# flat_bridge.net
KiCad netlist of a schematic drawn in EAGLE
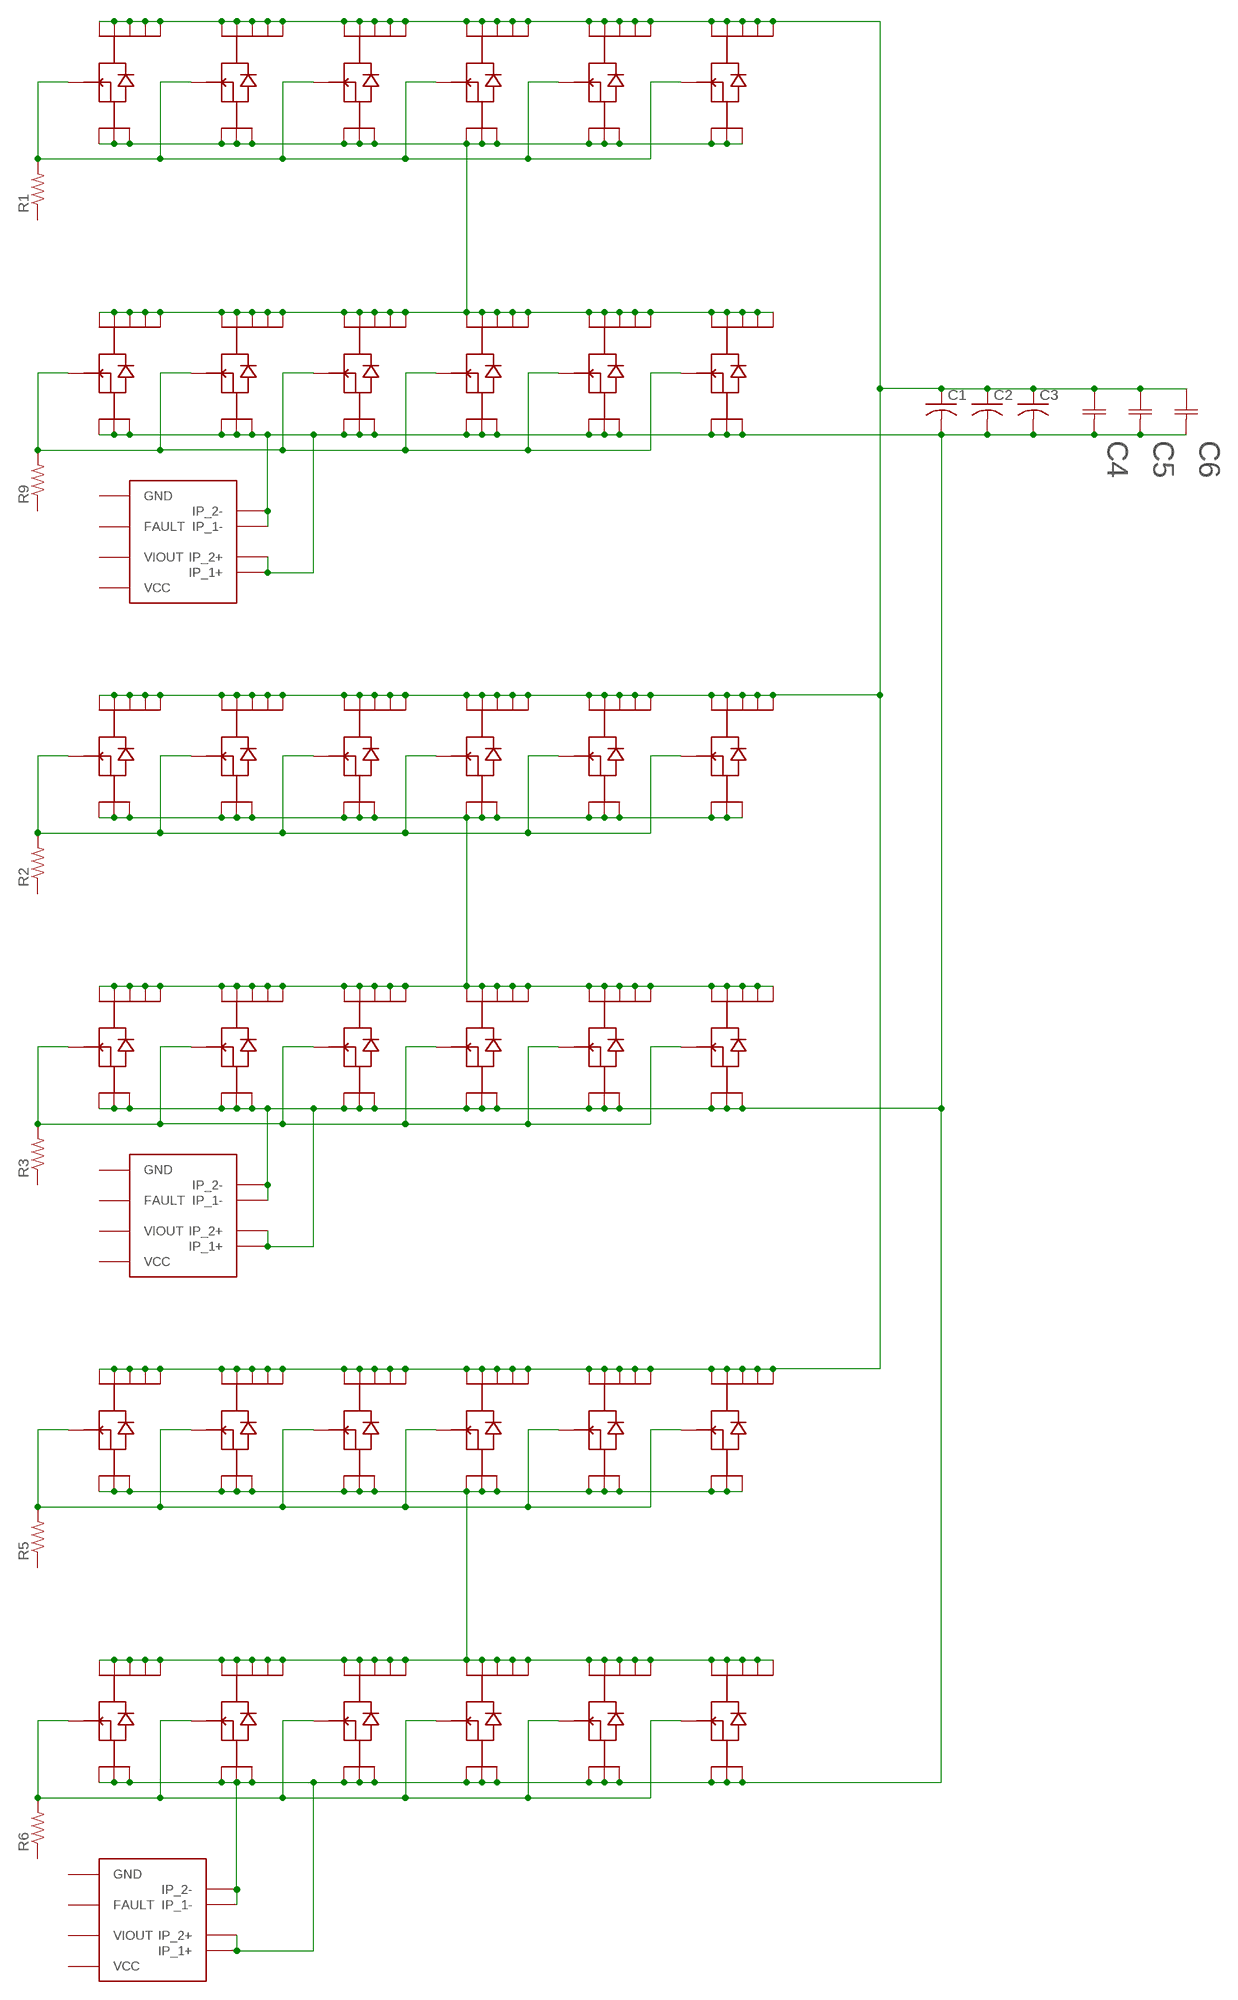
[diagram p0: schematic, sheet 1]

(export (version "E")
  (design (tool "Eeschema 10.0.6"))
  (components
    (comp (ref "C1")
      (value "C-USC2220K")
      (footprint "eagle-import:C2220K")
      (libsource (lib "eagle-import") (part "C-USC2220K"))
    )
    (comp (ref "C2")
      (value "C-USC2220K")
      (footprint "eagle-import:C2220K")
      (libsource (lib "eagle-import") (part "C-USC2220K"))
    )
    (comp (ref "C3")
      (value "C-USC2220K")
      (footprint "eagle-import:C2220K")
      (libsource (lib "eagle-import") (part "C-USC2220K"))
    )
    (comp (ref "C4")
      (value "EEVFK1J471M")
      (footprint "eagle-import:CAP_EEFK_J16")
      (fields (field (name "COPYRIGHT") "Copyright (C) 2015 Accelerated Designs. All rights reserved"))
      (libsource (lib "eagle-import") (part "EEVFK1J471M"))
    )
    (comp (ref "C5")
      (value "EEVFK1J471M")
      (footprint "eagle-import:CAP_EEFK_J16")
      (fields (field (name "COPYRIGHT") "Copyright (C) 2015 Accelerated Designs. All rights reserved"))
      (libsource (lib "eagle-import") (part "EEVFK1J471M"))
    )
    (comp (ref "C6")
      (value "EEVFK1J471M")
      (footprint "eagle-import:CAP_EEFK_J16")
      (fields (field (name "COPYRIGHT") "Copyright (C) 2015 Accelerated Designs. All rights reserved"))
      (libsource (lib "eagle-import") (part "EEVFK1J471M"))
    )
    (comp (ref "R1")
      (value "R-US_R1206")
      (footprint "eagle-import:R1206")
      (libsource (lib "eagle-import") (part "R-US_R1206"))
    )
    (comp (ref "R2")
      (value "R-US_R1206")
      (footprint "eagle-import:R1206")
      (libsource (lib "eagle-import") (part "R-US_R1206"))
    )
    (comp (ref "R3")
      (value "R-US_R1206")
      (footprint "eagle-import:R1206")
      (libsource (lib "eagle-import") (part "R-US_R1206"))
    )
    (comp (ref "R5")
      (value "R-US_R1206")
      (footprint "eagle-import:R1206")
      (libsource (lib "eagle-import") (part "R-US_R1206"))
    )
    (comp (ref "R6")
      (value "R-US_R1206")
      (footprint "eagle-import:R1206")
      (libsource (lib "eagle-import") (part "R-US_R1206"))
    )
    (comp (ref "R9")
      (value "R-US_R1206")
      (footprint "eagle-import:R1206")
      (libsource (lib "eagle-import") (part "R-US_R1206"))
    )
    (comp (ref "U$1")
      (value "TPH2R608NH")
      (footprint "eagle-import:SOP-ADVANCE")
      (libsource (lib "eagle-import") (part "TPH2R608NH"))
    )
    (comp (ref "U$2")
      (value "TPH2R608NH")
      (footprint "eagle-import:SOP-ADVANCE")
      (libsource (lib "eagle-import") (part "TPH2R608NH"))
    )
    (comp (ref "U$3")
      (value "TPH2R608NH")
      (footprint "eagle-import:SOP-ADVANCE")
      (libsource (lib "eagle-import") (part "TPH2R608NH"))
    )
    (comp (ref "U$4")
      (value "TPH2R608NH")
      (footprint "eagle-import:SOP-ADVANCE")
      (libsource (lib "eagle-import") (part "TPH2R608NH"))
    )
    (comp (ref "U$5")
      (value "TPH2R608NH")
      (footprint "eagle-import:SOP-ADVANCE")
      (libsource (lib "eagle-import") (part "TPH2R608NH"))
    )
    (comp (ref "U$6")
      (value "TPH2R608NH")
      (footprint "eagle-import:SOP-ADVANCE")
      (libsource (lib "eagle-import") (part "TPH2R608NH"))
    )
    (comp (ref "U$7")
      (value "ACS711")
      (footprint "eagle-import:SO8")
      (libsource (lib "eagle-import") (part "ACS711"))
    )
    (comp (ref "U$8")
      (value "TPH2R608NH")
      (footprint "eagle-import:SOP-ADVANCE")
      (libsource (lib "eagle-import") (part "TPH2R608NH"))
    )
    (comp (ref "U$9")
      (value "TPH2R608NH")
      (footprint "eagle-import:SOP-ADVANCE")
      (libsource (lib "eagle-import") (part "TPH2R608NH"))
    )
    (comp (ref "U$10")
      (value "TPH2R608NH")
      (footprint "eagle-import:SOP-ADVANCE")
      (libsource (lib "eagle-import") (part "TPH2R608NH"))
    )
    (comp (ref "U$11")
      (value "TPH2R608NH")
      (footprint "eagle-import:SOP-ADVANCE")
      (libsource (lib "eagle-import") (part "TPH2R608NH"))
    )
    (comp (ref "U$12")
      (value "TPH2R608NH")
      (footprint "eagle-import:SOP-ADVANCE")
      (libsource (lib "eagle-import") (part "TPH2R608NH"))
    )
    (comp (ref "U$13")
      (value "TPH2R608NH")
      (footprint "eagle-import:SOP-ADVANCE")
      (libsource (lib "eagle-import") (part "TPH2R608NH"))
    )
    (comp (ref "U$14")
      (value "TPH2R608NH")
      (footprint "eagle-import:SOP-ADVANCE")
      (libsource (lib "eagle-import") (part "TPH2R608NH"))
    )
    (comp (ref "U$15")
      (value "TPH2R608NH")
      (footprint "eagle-import:SOP-ADVANCE")
      (libsource (lib "eagle-import") (part "TPH2R608NH"))
    )
    (comp (ref "U$16")
      (value "TPH2R608NH")
      (footprint "eagle-import:SOP-ADVANCE")
      (libsource (lib "eagle-import") (part "TPH2R608NH"))
    )
    (comp (ref "U$17")
      (value "TPH2R608NH")
      (footprint "eagle-import:SOP-ADVANCE")
      (libsource (lib "eagle-import") (part "TPH2R608NH"))
    )
    (comp (ref "U$18")
      (value "TPH2R608NH")
      (footprint "eagle-import:SOP-ADVANCE")
      (libsource (lib "eagle-import") (part "TPH2R608NH"))
    )
    (comp (ref "U$19")
      (value "TPH2R608NH")
      (footprint "eagle-import:SOP-ADVANCE")
      (libsource (lib "eagle-import") (part "TPH2R608NH"))
    )
    (comp (ref "U$21")
      (value "TPH2R608NH")
      (footprint "eagle-import:SOP-ADVANCE")
      (libsource (lib "eagle-import") (part "TPH2R608NH"))
    )
    (comp (ref "U$22")
      (value "TPH2R608NH")
      (footprint "eagle-import:SOP-ADVANCE")
      (libsource (lib "eagle-import") (part "TPH2R608NH"))
    )
    (comp (ref "U$23")
      (value "TPH2R608NH")
      (footprint "eagle-import:SOP-ADVANCE")
      (libsource (lib "eagle-import") (part "TPH2R608NH"))
    )
    (comp (ref "U$24")
      (value "TPH2R608NH")
      (footprint "eagle-import:SOP-ADVANCE")
      (libsource (lib "eagle-import") (part "TPH2R608NH"))
    )
    (comp (ref "U$25")
      (value "TPH2R608NH")
      (footprint "eagle-import:SOP-ADVANCE")
      (libsource (lib "eagle-import") (part "TPH2R608NH"))
    )
    (comp (ref "U$26")
      (value "TPH2R608NH")
      (footprint "eagle-import:SOP-ADVANCE")
      (libsource (lib "eagle-import") (part "TPH2R608NH"))
    )
    (comp (ref "U$28")
      (value "ACS711")
      (footprint "eagle-import:SO8")
      (libsource (lib "eagle-import") (part "ACS711"))
    )
    (comp (ref "U$29")
      (value "TPH2R608NH")
      (footprint "eagle-import:SOP-ADVANCE")
      (libsource (lib "eagle-import") (part "TPH2R608NH"))
    )
    (comp (ref "U$30")
      (value "TPH2R608NH")
      (footprint "eagle-import:SOP-ADVANCE")
      (libsource (lib "eagle-import") (part "TPH2R608NH"))
    )
    (comp (ref "U$31")
      (value "TPH2R608NH")
      (footprint "eagle-import:SOP-ADVANCE")
      (libsource (lib "eagle-import") (part "TPH2R608NH"))
    )
    (comp (ref "U$32")
      (value "TPH2R608NH")
      (footprint "eagle-import:SOP-ADVANCE")
      (libsource (lib "eagle-import") (part "TPH2R608NH"))
    )
    (comp (ref "U$33")
      (value "TPH2R608NH")
      (footprint "eagle-import:SOP-ADVANCE")
      (libsource (lib "eagle-import") (part "TPH2R608NH"))
    )
    (comp (ref "U$34")
      (value "TPH2R608NH")
      (footprint "eagle-import:SOP-ADVANCE")
      (libsource (lib "eagle-import") (part "TPH2R608NH"))
    )
    (comp (ref "U$35")
      (value "TPH2R608NH")
      (footprint "eagle-import:SOP-ADVANCE")
      (libsource (lib "eagle-import") (part "TPH2R608NH"))
    )
    (comp (ref "U$36")
      (value "TPH2R608NH")
      (footprint "eagle-import:SOP-ADVANCE")
      (libsource (lib "eagle-import") (part "TPH2R608NH"))
    )
    (comp (ref "U$37")
      (value "TPH2R608NH")
      (footprint "eagle-import:SOP-ADVANCE")
      (libsource (lib "eagle-import") (part "TPH2R608NH"))
    )
    (comp (ref "U$38")
      (value "TPH2R608NH")
      (footprint "eagle-import:SOP-ADVANCE")
      (libsource (lib "eagle-import") (part "TPH2R608NH"))
    )
    (comp (ref "U$39")
      (value "TPH2R608NH")
      (footprint "eagle-import:SOP-ADVANCE")
      (libsource (lib "eagle-import") (part "TPH2R608NH"))
    )
    (comp (ref "U$40")
      (value "TPH2R608NH")
      (footprint "eagle-import:SOP-ADVANCE")
      (libsource (lib "eagle-import") (part "TPH2R608NH"))
    )
    (comp (ref "U$42")
      (value "ACS711")
      (footprint "eagle-import:SO8")
      (libsource (lib "eagle-import") (part "ACS711"))
    )
  )
  (nets
    (net (code "1") (name "Net-(C4-11)") (class "Default")
      (node (ref "C1") (pin "1") (pinfunction "1_1") (pintype "passive"))
      (node (ref "C2") (pin "1") (pinfunction "1_1") (pintype "passive"))
      (node (ref "C3") (pin "1") (pinfunction "1_1") (pintype "passive"))
      (node (ref "C4") (pin "1") (pinfunction "11_1") (pintype "passive"))
      (node (ref "C5") (pin "1") (pinfunction "11_1") (pintype "passive"))
      (node (ref "C6") (pin "1") (pinfunction "11_1") (pintype "passive"))
      (node (ref "U$1") (pin "5") (pinfunction "D1_5") (pintype "bidirectional"))
      (node (ref "U$1") (pin "6") (pinfunction "D2_6") (pintype "bidirectional"))
      (node (ref "U$1") (pin "7") (pinfunction "D3_7") (pintype "bidirectional"))
      (node (ref "U$1") (pin "8") (pinfunction "D4_8") (pintype "bidirectional"))
      (node (ref "U$1") (pin "9") (pinfunction "DTAB_9") (pintype "bidirectional"))
      (node (ref "U$15") (pin "5") (pinfunction "D1_5") (pintype "bidirectional"))
      (node (ref "U$15") (pin "6") (pinfunction "D2_6") (pintype "bidirectional"))
      (node (ref "U$15") (pin "7") (pinfunction "D3_7") (pintype "bidirectional"))
      (node (ref "U$15") (pin "8") (pinfunction "D4_8") (pintype "bidirectional"))
      (node (ref "U$15") (pin "9") (pinfunction "DTAB_9") (pintype "bidirectional"))
      (node (ref "U$16") (pin "5") (pinfunction "D1_5") (pintype "bidirectional"))
      (node (ref "U$16") (pin "6") (pinfunction "D2_6") (pintype "bidirectional"))
      (node (ref "U$16") (pin "7") (pinfunction "D3_7") (pintype "bidirectional"))
      (node (ref "U$16") (pin "8") (pinfunction "D4_8") (pintype "bidirectional"))
      (node (ref "U$16") (pin "9") (pinfunction "DTAB_9") (pintype "bidirectional"))
      (node (ref "U$17") (pin "5") (pinfunction "D1_5") (pintype "bidirectional"))
      (node (ref "U$17") (pin "6") (pinfunction "D2_6") (pintype "bidirectional"))
      (node (ref "U$17") (pin "7") (pinfunction "D3_7") (pintype "bidirectional"))
      (node (ref "U$17") (pin "8") (pinfunction "D4_8") (pintype "bidirectional"))
      (node (ref "U$17") (pin "9") (pinfunction "DTAB_9") (pintype "bidirectional"))
      (node (ref "U$18") (pin "5") (pinfunction "D1_5") (pintype "bidirectional"))
      (node (ref "U$18") (pin "6") (pinfunction "D2_6") (pintype "bidirectional"))
      (node (ref "U$18") (pin "7") (pinfunction "D3_7") (pintype "bidirectional"))
      (node (ref "U$18") (pin "8") (pinfunction "D4_8") (pintype "bidirectional"))
      (node (ref "U$18") (pin "9") (pinfunction "DTAB_9") (pintype "bidirectional"))
      (node (ref "U$19") (pin "5") (pinfunction "D1_5") (pintype "bidirectional"))
      (node (ref "U$19") (pin "6") (pinfunction "D2_6") (pintype "bidirectional"))
      (node (ref "U$19") (pin "7") (pinfunction "D3_7") (pintype "bidirectional"))
      (node (ref "U$19") (pin "8") (pinfunction "D4_8") (pintype "bidirectional"))
      (node (ref "U$19") (pin "9") (pinfunction "DTAB_9") (pintype "bidirectional"))
      (node (ref "U$2") (pin "5") (pinfunction "D1_5") (pintype "bidirectional"))
      (node (ref "U$2") (pin "6") (pinfunction "D2_6") (pintype "bidirectional"))
      (node (ref "U$2") (pin "7") (pinfunction "D3_7") (pintype "bidirectional"))
      (node (ref "U$2") (pin "8") (pinfunction "D4_8") (pintype "bidirectional"))
      (node (ref "U$2") (pin "9") (pinfunction "DTAB_9") (pintype "bidirectional"))
      (node (ref "U$29") (pin "5") (pinfunction "D1_5") (pintype "bidirectional"))
      (node (ref "U$29") (pin "6") (pinfunction "D2_6") (pintype "bidirectional"))
      (node (ref "U$29") (pin "7") (pinfunction "D3_7") (pintype "bidirectional"))
      (node (ref "U$29") (pin "8") (pinfunction "D4_8") (pintype "bidirectional"))
      (node (ref "U$29") (pin "9") (pinfunction "DTAB_9") (pintype "bidirectional"))
      (node (ref "U$3") (pin "5") (pinfunction "D1_5") (pintype "bidirectional"))
      (node (ref "U$3") (pin "6") (pinfunction "D2_6") (pintype "bidirectional"))
      (node (ref "U$3") (pin "7") (pinfunction "D3_7") (pintype "bidirectional"))
      (node (ref "U$3") (pin "8") (pinfunction "D4_8") (pintype "bidirectional"))
      (node (ref "U$3") (pin "9") (pinfunction "DTAB_9") (pintype "bidirectional"))
      (node (ref "U$30") (pin "5") (pinfunction "D1_5") (pintype "bidirectional"))
      (node (ref "U$30") (pin "6") (pinfunction "D2_6") (pintype "bidirectional"))
      (node (ref "U$30") (pin "7") (pinfunction "D3_7") (pintype "bidirectional"))
      (node (ref "U$30") (pin "8") (pinfunction "D4_8") (pintype "bidirectional"))
      (node (ref "U$30") (pin "9") (pinfunction "DTAB_9") (pintype "bidirectional"))
      (node (ref "U$31") (pin "5") (pinfunction "D1_5") (pintype "bidirectional"))
      (node (ref "U$31") (pin "6") (pinfunction "D2_6") (pintype "bidirectional"))
      (node (ref "U$31") (pin "7") (pinfunction "D3_7") (pintype "bidirectional"))
      (node (ref "U$31") (pin "8") (pinfunction "D4_8") (pintype "bidirectional"))
      (node (ref "U$31") (pin "9") (pinfunction "DTAB_9") (pintype "bidirectional"))
      (node (ref "U$32") (pin "5") (pinfunction "D1_5") (pintype "bidirectional"))
      (node (ref "U$32") (pin "6") (pinfunction "D2_6") (pintype "bidirectional"))
      (node (ref "U$32") (pin "7") (pinfunction "D3_7") (pintype "bidirectional"))
      (node (ref "U$32") (pin "8") (pinfunction "D4_8") (pintype "bidirectional"))
      (node (ref "U$32") (pin "9") (pinfunction "DTAB_9") (pintype "bidirectional"))
      (node (ref "U$33") (pin "5") (pinfunction "D1_5") (pintype "bidirectional"))
      (node (ref "U$33") (pin "6") (pinfunction "D2_6") (pintype "bidirectional"))
      (node (ref "U$33") (pin "7") (pinfunction "D3_7") (pintype "bidirectional"))
      (node (ref "U$33") (pin "8") (pinfunction "D4_8") (pintype "bidirectional"))
      (node (ref "U$33") (pin "9") (pinfunction "DTAB_9") (pintype "bidirectional"))
      (node (ref "U$34") (pin "5") (pinfunction "D1_5") (pintype "bidirectional"))
      (node (ref "U$34") (pin "6") (pinfunction "D2_6") (pintype "bidirectional"))
      (node (ref "U$34") (pin "7") (pinfunction "D3_7") (pintype "bidirectional"))
      (node (ref "U$34") (pin "8") (pinfunction "D4_8") (pintype "bidirectional"))
      (node (ref "U$34") (pin "9") (pinfunction "DTAB_9") (pintype "bidirectional"))
      (node (ref "U$4") (pin "5") (pinfunction "D1_5") (pintype "bidirectional"))
      (node (ref "U$4") (pin "6") (pinfunction "D2_6") (pintype "bidirectional"))
      (node (ref "U$4") (pin "7") (pinfunction "D3_7") (pintype "bidirectional"))
      (node (ref "U$4") (pin "8") (pinfunction "D4_8") (pintype "bidirectional"))
      (node (ref "U$4") (pin "9") (pinfunction "DTAB_9") (pintype "bidirectional"))
      (node (ref "U$5") (pin "5") (pinfunction "D1_5") (pintype "bidirectional"))
      (node (ref "U$5") (pin "6") (pinfunction "D2_6") (pintype "bidirectional"))
      (node (ref "U$5") (pin "7") (pinfunction "D3_7") (pintype "bidirectional"))
      (node (ref "U$5") (pin "8") (pinfunction "D4_8") (pintype "bidirectional"))
      (node (ref "U$5") (pin "9") (pinfunction "DTAB_9") (pintype "bidirectional"))
      (node (ref "U$6") (pin "5") (pinfunction "D1_5") (pintype "bidirectional"))
      (node (ref "U$6") (pin "6") (pinfunction "D2_6") (pintype "bidirectional"))
      (node (ref "U$6") (pin "7") (pinfunction "D3_7") (pintype "bidirectional"))
      (node (ref "U$6") (pin "8") (pinfunction "D4_8") (pintype "bidirectional"))
      (node (ref "U$6") (pin "9") (pinfunction "DTAB_9") (pintype "bidirectional"))
      (node (ref "U$8") (pin "5") (pinfunction "D1_5") (pintype "bidirectional"))
      (node (ref "U$8") (pin "6") (pinfunction "D2_6") (pintype "bidirectional"))
      (node (ref "U$8") (pin "7") (pinfunction "D3_7") (pintype "bidirectional"))
      (node (ref "U$8") (pin "8") (pinfunction "D4_8") (pintype "bidirectional"))
      (node (ref "U$8") (pin "9") (pinfunction "DTAB_9") (pintype "bidirectional"))
    )
    (net (code "2") (name "Net-(C4-22)") (class "Default")
      (node (ref "C1") (pin "2") (pinfunction "2_2") (pintype "passive"))
      (node (ref "C2") (pin "2") (pinfunction "2_2") (pintype "passive"))
      (node (ref "C3") (pin "2") (pinfunction "2_2") (pintype "passive"))
      (node (ref "C4") (pin "2") (pinfunction "22_2") (pintype "passive"))
      (node (ref "C5") (pin "2") (pinfunction "22_2") (pintype "passive"))
      (node (ref "C6") (pin "2") (pinfunction "22_2") (pintype "passive"))
      (node (ref "U$10") (pin "1") (pinfunction "S1_1") (pintype "bidirectional"))
      (node (ref "U$10") (pin "2") (pinfunction "S2_2") (pintype "bidirectional"))
      (node (ref "U$10") (pin "3") (pinfunction "S3_3") (pintype "bidirectional"))
      (node (ref "U$11") (pin "1") (pinfunction "S1_1") (pintype "bidirectional"))
      (node (ref "U$11") (pin "2") (pinfunction "S2_2") (pintype "bidirectional"))
      (node (ref "U$11") (pin "3") (pinfunction "S3_3") (pintype "bidirectional"))
      (node (ref "U$12") (pin "1") (pinfunction "S1_1") (pintype "bidirectional"))
      (node (ref "U$12") (pin "2") (pinfunction "S2_2") (pintype "bidirectional"))
      (node (ref "U$12") (pin "3") (pinfunction "S3_3") (pintype "bidirectional"))
      (node (ref "U$13") (pin "1") (pinfunction "S1_1") (pintype "bidirectional"))
      (node (ref "U$13") (pin "2") (pinfunction "S2_2") (pintype "bidirectional"))
      (node (ref "U$13") (pin "3") (pinfunction "S3_3") (pintype "bidirectional"))
      (node (ref "U$14") (pin "1") (pinfunction "S1_1") (pintype "bidirectional"))
      (node (ref "U$14") (pin "2") (pinfunction "S2_2") (pintype "bidirectional"))
      (node (ref "U$14") (pin "3") (pinfunction "S3_3") (pintype "bidirectional"))
      (node (ref "U$21") (pin "1") (pinfunction "S1_1") (pintype "bidirectional"))
      (node (ref "U$21") (pin "2") (pinfunction "S2_2") (pintype "bidirectional"))
      (node (ref "U$21") (pin "3") (pinfunction "S3_3") (pintype "bidirectional"))
      (node (ref "U$22") (pin "1") (pinfunction "S1_1") (pintype "bidirectional"))
      (node (ref "U$22") (pin "2") (pinfunction "S2_2") (pintype "bidirectional"))
      (node (ref "U$22") (pin "3") (pinfunction "S3_3") (pintype "bidirectional"))
      (node (ref "U$23") (pin "1") (pinfunction "S1_1") (pintype "bidirectional"))
      (node (ref "U$23") (pin "2") (pinfunction "S2_2") (pintype "bidirectional"))
      (node (ref "U$23") (pin "3") (pinfunction "S3_3") (pintype "bidirectional"))
      (node (ref "U$24") (pin "1") (pinfunction "S1_1") (pintype "bidirectional"))
      (node (ref "U$24") (pin "2") (pinfunction "S2_2") (pintype "bidirectional"))
      (node (ref "U$24") (pin "3") (pinfunction "S3_3") (pintype "bidirectional"))
      (node (ref "U$25") (pin "1") (pinfunction "S1_1") (pintype "bidirectional"))
      (node (ref "U$25") (pin "2") (pinfunction "S2_2") (pintype "bidirectional"))
      (node (ref "U$25") (pin "3") (pinfunction "S3_3") (pintype "bidirectional"))
      (node (ref "U$26") (pin "1") (pinfunction "S1_1") (pintype "bidirectional"))
      (node (ref "U$26") (pin "2") (pinfunction "S2_2") (pintype "bidirectional"))
      (node (ref "U$26") (pin "3") (pinfunction "S3_3") (pintype "bidirectional"))
      (node (ref "U$28") (pin "1") (pinfunction "IP_1+_1") (pintype "bidirectional"))
      (node (ref "U$28") (pin "2") (pinfunction "IP_2+_2") (pintype "bidirectional"))
      (node (ref "U$28") (pin "3") (pinfunction "IP_1-_3") (pintype "bidirectional"))
      (node (ref "U$28") (pin "4") (pinfunction "IP_2-_4") (pintype "bidirectional"))
      (node (ref "U$35") (pin "1") (pinfunction "S1_1") (pintype "bidirectional"))
      (node (ref "U$35") (pin "2") (pinfunction "S2_2") (pintype "bidirectional"))
      (node (ref "U$35") (pin "3") (pinfunction "S3_3") (pintype "bidirectional"))
      (node (ref "U$36") (pin "1") (pinfunction "S1_1") (pintype "bidirectional"))
      (node (ref "U$36") (pin "2") (pinfunction "S2_2") (pintype "bidirectional"))
      (node (ref "U$36") (pin "3") (pinfunction "S3_3") (pintype "bidirectional"))
      (node (ref "U$37") (pin "1") (pinfunction "S1_1") (pintype "bidirectional"))
      (node (ref "U$37") (pin "2") (pinfunction "S2_2") (pintype "bidirectional"))
      (node (ref "U$37") (pin "3") (pinfunction "S3_3") (pintype "bidirectional"))
      (node (ref "U$38") (pin "1") (pinfunction "S1_1") (pintype "bidirectional"))
      (node (ref "U$38") (pin "2") (pinfunction "S2_2") (pintype "bidirectional"))
      (node (ref "U$38") (pin "3") (pinfunction "S3_3") (pintype "bidirectional"))
      (node (ref "U$39") (pin "1") (pinfunction "S1_1") (pintype "bidirectional"))
      (node (ref "U$39") (pin "2") (pinfunction "S2_2") (pintype "bidirectional"))
      (node (ref "U$39") (pin "3") (pinfunction "S3_3") (pintype "bidirectional"))
      (node (ref "U$40") (pin "1") (pinfunction "S1_1") (pintype "bidirectional"))
      (node (ref "U$40") (pin "2") (pinfunction "S2_2") (pintype "bidirectional"))
      (node (ref "U$40") (pin "3") (pinfunction "S3_3") (pintype "bidirectional"))
      (node (ref "U$42") (pin "1") (pinfunction "IP_1+_1") (pintype "bidirectional"))
      (node (ref "U$42") (pin "2") (pinfunction "IP_2+_2") (pintype "bidirectional"))
      (node (ref "U$42") (pin "3") (pinfunction "IP_1-_3") (pintype "bidirectional"))
      (node (ref "U$42") (pin "4") (pinfunction "IP_2-_4") (pintype "bidirectional"))
      (node (ref "U$7") (pin "1") (pinfunction "IP_1+_1") (pintype "bidirectional"))
      (node (ref "U$7") (pin "2") (pinfunction "IP_2+_2") (pintype "bidirectional"))
      (node (ref "U$7") (pin "3") (pinfunction "IP_1-_3") (pintype "bidirectional"))
      (node (ref "U$7") (pin "4") (pinfunction "IP_2-_4") (pintype "bidirectional"))
      (node (ref "U$9") (pin "1") (pinfunction "S1_1") (pintype "bidirectional"))
      (node (ref "U$9") (pin "2") (pinfunction "S2_2") (pintype "bidirectional"))
      (node (ref "U$9") (pin "3") (pinfunction "S3_3") (pintype "bidirectional"))
    )
    (net (code "3") (name "Net-(U$1-G)") (class "Default")
      (node (ref "R1") (pin "2") (pinfunction "2_2") (pintype "passive"))
      (node (ref "U$1") (pin "4") (pinfunction "G_4") (pintype "bidirectional"))
      (node (ref "U$2") (pin "4") (pinfunction "G_4") (pintype "bidirectional"))
      (node (ref "U$3") (pin "4") (pinfunction "G_4") (pintype "bidirectional"))
      (node (ref "U$4") (pin "4") (pinfunction "G_4") (pintype "bidirectional"))
      (node (ref "U$5") (pin "4") (pinfunction "G_4") (pintype "bidirectional"))
      (node (ref "U$6") (pin "4") (pinfunction "G_4") (pintype "bidirectional"))
    )
    (net (code "4") (name "Net-(U$1-S1)") (class "Default")
      (node (ref "U$1") (pin "1") (pinfunction "S1_1") (pintype "bidirectional"))
      (node (ref "U$1") (pin "2") (pinfunction "S2_2") (pintype "bidirectional"))
      (node (ref "U$1") (pin "3") (pinfunction "S3_3") (pintype "bidirectional"))
      (node (ref "U$10") (pin "5") (pinfunction "D1_5") (pintype "bidirectional"))
      (node (ref "U$10") (pin "6") (pinfunction "D2_6") (pintype "bidirectional"))
      (node (ref "U$10") (pin "7") (pinfunction "D3_7") (pintype "bidirectional"))
      (node (ref "U$10") (pin "8") (pinfunction "D4_8") (pintype "bidirectional"))
      (node (ref "U$10") (pin "9") (pinfunction "DTAB_9") (pintype "bidirectional"))
      (node (ref "U$11") (pin "5") (pinfunction "D1_5") (pintype "bidirectional"))
      (node (ref "U$11") (pin "6") (pinfunction "D2_6") (pintype "bidirectional"))
      (node (ref "U$11") (pin "7") (pinfunction "D3_7") (pintype "bidirectional"))
      (node (ref "U$11") (pin "8") (pinfunction "D4_8") (pintype "bidirectional"))
      (node (ref "U$11") (pin "9") (pinfunction "DTAB_9") (pintype "bidirectional"))
      (node (ref "U$12") (pin "5") (pinfunction "D1_5") (pintype "bidirectional"))
      (node (ref "U$12") (pin "6") (pinfunction "D2_6") (pintype "bidirectional"))
      (node (ref "U$12") (pin "7") (pinfunction "D3_7") (pintype "bidirectional"))
      (node (ref "U$12") (pin "8") (pinfunction "D4_8") (pintype "bidirectional"))
      (node (ref "U$12") (pin "9") (pinfunction "DTAB_9") (pintype "bidirectional"))
      (node (ref "U$13") (pin "5") (pinfunction "D1_5") (pintype "bidirectional"))
      (node (ref "U$13") (pin "6") (pinfunction "D2_6") (pintype "bidirectional"))
      (node (ref "U$13") (pin "7") (pinfunction "D3_7") (pintype "bidirectional"))
      (node (ref "U$13") (pin "8") (pinfunction "D4_8") (pintype "bidirectional"))
      (node (ref "U$13") (pin "9") (pinfunction "DTAB_9") (pintype "bidirectional"))
      (node (ref "U$14") (pin "5") (pinfunction "D1_5") (pintype "bidirectional"))
      (node (ref "U$14") (pin "6") (pinfunction "D2_6") (pintype "bidirectional"))
      (node (ref "U$14") (pin "7") (pinfunction "D3_7") (pintype "bidirectional"))
      (node (ref "U$14") (pin "8") (pinfunction "D4_8") (pintype "bidirectional"))
      (node (ref "U$14") (pin "9") (pinfunction "DTAB_9") (pintype "bidirectional"))
      (node (ref "U$2") (pin "1") (pinfunction "S1_1") (pintype "bidirectional"))
      (node (ref "U$2") (pin "2") (pinfunction "S2_2") (pintype "bidirectional"))
      (node (ref "U$2") (pin "3") (pinfunction "S3_3") (pintype "bidirectional"))
      (node (ref "U$3") (pin "1") (pinfunction "S1_1") (pintype "bidirectional"))
      (node (ref "U$3") (pin "2") (pinfunction "S2_2") (pintype "bidirectional"))
      (node (ref "U$3") (pin "3") (pinfunction "S3_3") (pintype "bidirectional"))
      (node (ref "U$4") (pin "1") (pinfunction "S1_1") (pintype "bidirectional"))
      (node (ref "U$4") (pin "2") (pinfunction "S2_2") (pintype "bidirectional"))
      (node (ref "U$4") (pin "3") (pinfunction "S3_3") (pintype "bidirectional"))
      (node (ref "U$5") (pin "1") (pinfunction "S1_1") (pintype "bidirectional"))
      (node (ref "U$5") (pin "2") (pinfunction "S2_2") (pintype "bidirectional"))
      (node (ref "U$5") (pin "3") (pinfunction "S3_3") (pintype "bidirectional"))
      (node (ref "U$6") (pin "1") (pinfunction "S1_1") (pintype "bidirectional"))
      (node (ref "U$6") (pin "2") (pinfunction "S2_2") (pintype "bidirectional"))
      (node (ref "U$6") (pin "3") (pinfunction "S3_3") (pintype "bidirectional"))
      (node (ref "U$9") (pin "5") (pinfunction "D1_5") (pintype "bidirectional"))
      (node (ref "U$9") (pin "6") (pinfunction "D2_6") (pintype "bidirectional"))
      (node (ref "U$9") (pin "7") (pinfunction "D3_7") (pintype "bidirectional"))
      (node (ref "U$9") (pin "8") (pinfunction "D4_8") (pintype "bidirectional"))
      (node (ref "U$9") (pin "9") (pinfunction "DTAB_9") (pintype "bidirectional"))
    )
    (net (code "5") (name "Net-(U$10-G)") (class "Default")
      (node (ref "R9") (pin "2") (pinfunction "2_2") (pintype "passive"))
      (node (ref "U$10") (pin "4") (pinfunction "G_4") (pintype "bidirectional"))
      (node (ref "U$11") (pin "4") (pinfunction "G_4") (pintype "bidirectional"))
      (node (ref "U$12") (pin "4") (pinfunction "G_4") (pintype "bidirectional"))
      (node (ref "U$13") (pin "4") (pinfunction "G_4") (pintype "bidirectional"))
      (node (ref "U$14") (pin "4") (pinfunction "G_4") (pintype "bidirectional"))
      (node (ref "U$9") (pin "4") (pinfunction "G_4") (pintype "bidirectional"))
    )
    (net (code "6") (name "Net-(U$15-G)") (class "Default")
      (node (ref "R2") (pin "2") (pinfunction "2_2") (pintype "passive"))
      (node (ref "U$15") (pin "4") (pinfunction "G_4") (pintype "bidirectional"))
      (node (ref "U$16") (pin "4") (pinfunction "G_4") (pintype "bidirectional"))
      (node (ref "U$17") (pin "4") (pinfunction "G_4") (pintype "bidirectional"))
      (node (ref "U$18") (pin "4") (pinfunction "G_4") (pintype "bidirectional"))
      (node (ref "U$19") (pin "4") (pinfunction "G_4") (pintype "bidirectional"))
      (node (ref "U$8") (pin "4") (pinfunction "G_4") (pintype "bidirectional"))
    )
    (net (code "7") (name "Net-(U$15-S1)") (class "Default")
      (node (ref "U$15") (pin "1") (pinfunction "S1_1") (pintype "bidirectional"))
      (node (ref "U$15") (pin "2") (pinfunction "S2_2") (pintype "bidirectional"))
      (node (ref "U$15") (pin "3") (pinfunction "S3_3") (pintype "bidirectional"))
      (node (ref "U$16") (pin "1") (pinfunction "S1_1") (pintype "bidirectional"))
      (node (ref "U$16") (pin "2") (pinfunction "S2_2") (pintype "bidirectional"))
      (node (ref "U$16") (pin "3") (pinfunction "S3_3") (pintype "bidirectional"))
      (node (ref "U$17") (pin "1") (pinfunction "S1_1") (pintype "bidirectional"))
      (node (ref "U$17") (pin "2") (pinfunction "S2_2") (pintype "bidirectional"))
      (node (ref "U$17") (pin "3") (pinfunction "S3_3") (pintype "bidirectional"))
      (node (ref "U$18") (pin "1") (pinfunction "S1_1") (pintype "bidirectional"))
      (node (ref "U$18") (pin "2") (pinfunction "S2_2") (pintype "bidirectional"))
      (node (ref "U$18") (pin "3") (pinfunction "S3_3") (pintype "bidirectional"))
      (node (ref "U$19") (pin "1") (pinfunction "S1_1") (pintype "bidirectional"))
      (node (ref "U$19") (pin "2") (pinfunction "S2_2") (pintype "bidirectional"))
      (node (ref "U$19") (pin "3") (pinfunction "S3_3") (pintype "bidirectional"))
      (node (ref "U$21") (pin "5") (pinfunction "D1_5") (pintype "bidirectional"))
      (node (ref "U$21") (pin "6") (pinfunction "D2_6") (pintype "bidirectional"))
      (node (ref "U$21") (pin "7") (pinfunction "D3_7") (pintype "bidirectional"))
      (node (ref "U$21") (pin "8") (pinfunction "D4_8") (pintype "bidirectional"))
      (node (ref "U$21") (pin "9") (pinfunction "DTAB_9") (pintype "bidirectional"))
      (node (ref "U$22") (pin "5") (pinfunction "D1_5") (pintype "bidirectional"))
      (node (ref "U$22") (pin "6") (pinfunction "D2_6") (pintype "bidirectional"))
      (node (ref "U$22") (pin "7") (pinfunction "D3_7") (pintype "bidirectional"))
      (node (ref "U$22") (pin "8") (pinfunction "D4_8") (pintype "bidirectional"))
      (node (ref "U$22") (pin "9") (pinfunction "DTAB_9") (pintype "bidirectional"))
      (node (ref "U$23") (pin "5") (pinfunction "D1_5") (pintype "bidirectional"))
      (node (ref "U$23") (pin "6") (pinfunction "D2_6") (pintype "bidirectional"))
      (node (ref "U$23") (pin "7") (pinfunction "D3_7") (pintype "bidirectional"))
      (node (ref "U$23") (pin "8") (pinfunction "D4_8") (pintype "bidirectional"))
      (node (ref "U$23") (pin "9") (pinfunction "DTAB_9") (pintype "bidirectional"))
      (node (ref "U$24") (pin "5") (pinfunction "D1_5") (pintype "bidirectional"))
      (node (ref "U$24") (pin "6") (pinfunction "D2_6") (pintype "bidirectional"))
      (node (ref "U$24") (pin "7") (pinfunction "D3_7") (pintype "bidirectional"))
      (node (ref "U$24") (pin "8") (pinfunction "D4_8") (pintype "bidirectional"))
      (node (ref "U$24") (pin "9") (pinfunction "DTAB_9") (pintype "bidirectional"))
      (node (ref "U$25") (pin "5") (pinfunction "D1_5") (pintype "bidirectional"))
      (node (ref "U$25") (pin "6") (pinfunction "D2_6") (pintype "bidirectional"))
      (node (ref "U$25") (pin "7") (pinfunction "D3_7") (pintype "bidirectional"))
      (node (ref "U$25") (pin "8") (pinfunction "D4_8") (pintype "bidirectional"))
      (node (ref "U$25") (pin "9") (pinfunction "DTAB_9") (pintype "bidirectional"))
      (node (ref "U$26") (pin "5") (pinfunction "D1_5") (pintype "bidirectional"))
      (node (ref "U$26") (pin "6") (pinfunction "D2_6") (pintype "bidirectional"))
      (node (ref "U$26") (pin "7") (pinfunction "D3_7") (pintype "bidirectional"))
      (node (ref "U$26") (pin "8") (pinfunction "D4_8") (pintype "bidirectional"))
      (node (ref "U$26") (pin "9") (pinfunction "DTAB_9") (pintype "bidirectional"))
      (node (ref "U$8") (pin "1") (pinfunction "S1_1") (pintype "bidirectional"))
      (node (ref "U$8") (pin "2") (pinfunction "S2_2") (pintype "bidirectional"))
      (node (ref "U$8") (pin "3") (pinfunction "S3_3") (pintype "bidirectional"))
    )
    (net (code "8") (name "Net-(U$21-G)") (class "Default")
      (node (ref "R3") (pin "2") (pinfunction "2_2") (pintype "passive"))
      (node (ref "U$21") (pin "4") (pinfunction "G_4") (pintype "bidirectional"))
      (node (ref "U$22") (pin "4") (pinfunction "G_4") (pintype "bidirectional"))
      (node (ref "U$23") (pin "4") (pinfunction "G_4") (pintype "bidirectional"))
      (node (ref "U$24") (pin "4") (pinfunction "G_4") (pintype "bidirectional"))
      (node (ref "U$25") (pin "4") (pinfunction "G_4") (pintype "bidirectional"))
      (node (ref "U$26") (pin "4") (pinfunction "G_4") (pintype "bidirectional"))
    )
    (net (code "9") (name "Net-(U$29-G)") (class "Default")
      (node (ref "R5") (pin "2") (pinfunction "2_2") (pintype "passive"))
      (node (ref "U$29") (pin "4") (pinfunction "G_4") (pintype "bidirectional"))
      (node (ref "U$30") (pin "4") (pinfunction "G_4") (pintype "bidirectional"))
      (node (ref "U$31") (pin "4") (pinfunction "G_4") (pintype "bidirectional"))
      (node (ref "U$32") (pin "4") (pinfunction "G_4") (pintype "bidirectional"))
      (node (ref "U$33") (pin "4") (pinfunction "G_4") (pintype "bidirectional"))
      (node (ref "U$34") (pin "4") (pinfunction "G_4") (pintype "bidirectional"))
    )
    (net (code "10") (name "Net-(U$29-S1)") (class "Default")
      (node (ref "U$29") (pin "1") (pinfunction "S1_1") (pintype "bidirectional"))
      (node (ref "U$29") (pin "2") (pinfunction "S2_2") (pintype "bidirectional"))
      (node (ref "U$29") (pin "3") (pinfunction "S3_3") (pintype "bidirectional"))
      (node (ref "U$30") (pin "1") (pinfunction "S1_1") (pintype "bidirectional"))
      (node (ref "U$30") (pin "2") (pinfunction "S2_2") (pintype "bidirectional"))
      (node (ref "U$30") (pin "3") (pinfunction "S3_3") (pintype "bidirectional"))
      (node (ref "U$31") (pin "1") (pinfunction "S1_1") (pintype "bidirectional"))
      (node (ref "U$31") (pin "2") (pinfunction "S2_2") (pintype "bidirectional"))
      (node (ref "U$31") (pin "3") (pinfunction "S3_3") (pintype "bidirectional"))
      (node (ref "U$32") (pin "1") (pinfunction "S1_1") (pintype "bidirectional"))
      (node (ref "U$32") (pin "2") (pinfunction "S2_2") (pintype "bidirectional"))
      (node (ref "U$32") (pin "3") (pinfunction "S3_3") (pintype "bidirectional"))
      (node (ref "U$33") (pin "1") (pinfunction "S1_1") (pintype "bidirectional"))
      (node (ref "U$33") (pin "2") (pinfunction "S2_2") (pintype "bidirectional"))
      (node (ref "U$33") (pin "3") (pinfunction "S3_3") (pintype "bidirectional"))
      (node (ref "U$34") (pin "1") (pinfunction "S1_1") (pintype "bidirectional"))
      (node (ref "U$34") (pin "2") (pinfunction "S2_2") (pintype "bidirectional"))
      (node (ref "U$34") (pin "3") (pinfunction "S3_3") (pintype "bidirectional"))
      (node (ref "U$35") (pin "5") (pinfunction "D1_5") (pintype "bidirectional"))
      (node (ref "U$35") (pin "6") (pinfunction "D2_6") (pintype "bidirectional"))
      (node (ref "U$35") (pin "7") (pinfunction "D3_7") (pintype "bidirectional"))
      (node (ref "U$35") (pin "8") (pinfunction "D4_8") (pintype "bidirectional"))
      (node (ref "U$35") (pin "9") (pinfunction "DTAB_9") (pintype "bidirectional"))
      (node (ref "U$36") (pin "5") (pinfunction "D1_5") (pintype "bidirectional"))
      (node (ref "U$36") (pin "6") (pinfunction "D2_6") (pintype "bidirectional"))
      (node (ref "U$36") (pin "7") (pinfunction "D3_7") (pintype "bidirectional"))
      (node (ref "U$36") (pin "8") (pinfunction "D4_8") (pintype "bidirectional"))
      (node (ref "U$36") (pin "9") (pinfunction "DTAB_9") (pintype "bidirectional"))
      (node (ref "U$37") (pin "5") (pinfunction "D1_5") (pintype "bidirectional"))
      (node (ref "U$37") (pin "6") (pinfunction "D2_6") (pintype "bidirectional"))
      (node (ref "U$37") (pin "7") (pinfunction "D3_7") (pintype "bidirectional"))
      (node (ref "U$37") (pin "8") (pinfunction "D4_8") (pintype "bidirectional"))
      (node (ref "U$37") (pin "9") (pinfunction "DTAB_9") (pintype "bidirectional"))
      (node (ref "U$38") (pin "5") (pinfunction "D1_5") (pintype "bidirectional"))
      (node (ref "U$38") (pin "6") (pinfunction "D2_6") (pintype "bidirectional"))
      (node (ref "U$38") (pin "7") (pinfunction "D3_7") (pintype "bidirectional"))
      (node (ref "U$38") (pin "8") (pinfunction "D4_8") (pintype "bidirectional"))
      (node (ref "U$38") (pin "9") (pinfunction "DTAB_9") (pintype "bidirectional"))
      (node (ref "U$39") (pin "5") (pinfunction "D1_5") (pintype "bidirectional"))
      (node (ref "U$39") (pin "6") (pinfunction "D2_6") (pintype "bidirectional"))
      (node (ref "U$39") (pin "7") (pinfunction "D3_7") (pintype "bidirectional"))
      (node (ref "U$39") (pin "8") (pinfunction "D4_8") (pintype "bidirectional"))
      (node (ref "U$39") (pin "9") (pinfunction "DTAB_9") (pintype "bidirectional"))
      (node (ref "U$40") (pin "5") (pinfunction "D1_5") (pintype "bidirectional"))
      (node (ref "U$40") (pin "6") (pinfunction "D2_6") (pintype "bidirectional"))
      (node (ref "U$40") (pin "7") (pinfunction "D3_7") (pintype "bidirectional"))
      (node (ref "U$40") (pin "8") (pinfunction "D4_8") (pintype "bidirectional"))
      (node (ref "U$40") (pin "9") (pinfunction "DTAB_9") (pintype "bidirectional"))
    )
    (net (code "11") (name "Net-(U$35-G)") (class "Default")
      (node (ref "R6") (pin "2") (pinfunction "2_2") (pintype "passive"))
      (node (ref "U$35") (pin "4") (pinfunction "G_4") (pintype "bidirectional"))
      (node (ref "U$36") (pin "4") (pinfunction "G_4") (pintype "bidirectional"))
      (node (ref "U$37") (pin "4") (pinfunction "G_4") (pintype "bidirectional"))
      (node (ref "U$38") (pin "4") (pinfunction "G_4") (pintype "bidirectional"))
      (node (ref "U$39") (pin "4") (pinfunction "G_4") (pintype "bidirectional"))
      (node (ref "U$40") (pin "4") (pinfunction "G_4") (pintype "bidirectional"))
    )
    (net (code "12") (name "unconnected-(R1-Pad1)") (class "Default")
      (node (ref "R1") (pin "1") (pinfunction "1_1") (pintype "passive"))
    )
    (net (code "13") (name "unconnected-(R2-Pad1)") (class "Default")
      (node (ref "R2") (pin "1") (pinfunction "1_1") (pintype "passive"))
    )
    (net (code "14") (name "unconnected-(R3-Pad1)") (class "Default")
      (node (ref "R3") (pin "1") (pinfunction "1_1") (pintype "passive"))
    )
    (net (code "15") (name "unconnected-(R5-Pad1)") (class "Default")
      (node (ref "R5") (pin "1") (pinfunction "1_1") (pintype "passive"))
    )
    (net (code "16") (name "unconnected-(R6-Pad1)") (class "Default")
      (node (ref "R6") (pin "1") (pinfunction "1_1") (pintype "passive"))
    )
    (net (code "17") (name "unconnected-(R9-Pad1)") (class "Default")
      (node (ref "R9") (pin "1") (pinfunction "1_1") (pintype "passive"))
    )
    (net (code "18") (name "unconnected-(U$7-FAULT-Pad6)") (class "Default")
      (node (ref "U$7") (pin "6") (pinfunction "FAULT_6") (pintype "bidirectional"))
    )
    (net (code "19") (name "unconnected-(U$7-GND-Pad5)") (class "Default")
      (node (ref "U$7") (pin "5") (pinfunction "GND_5") (pintype "bidirectional"))
    )
    (net (code "20") (name "unconnected-(U$7-VCC-Pad8)") (class "Default")
      (node (ref "U$7") (pin "8") (pinfunction "VCC_8") (pintype "bidirectional"))
    )
    (net (code "21") (name "unconnected-(U$7-VIOUT-Pad7)") (class "Default")
      (node (ref "U$7") (pin "7") (pinfunction "VIOUT_7") (pintype "bidirectional"))
    )
    (net (code "22") (name "unconnected-(U$28-FAULT-Pad6)") (class "Default")
      (node (ref "U$28") (pin "6") (pinfunction "FAULT_6") (pintype "bidirectional"))
    )
    (net (code "23") (name "unconnected-(U$28-GND-Pad5)") (class "Default")
      (node (ref "U$28") (pin "5") (pinfunction "GND_5") (pintype "bidirectional"))
    )
    (net (code "24") (name "unconnected-(U$28-VCC-Pad8)") (class "Default")
      (node (ref "U$28") (pin "8") (pinfunction "VCC_8") (pintype "bidirectional"))
    )
    (net (code "25") (name "unconnected-(U$28-VIOUT-Pad7)") (class "Default")
      (node (ref "U$28") (pin "7") (pinfunction "VIOUT_7") (pintype "bidirectional"))
    )
    (net (code "26") (name "unconnected-(U$42-FAULT-Pad6)") (class "Default")
      (node (ref "U$42") (pin "6") (pinfunction "FAULT_6") (pintype "bidirectional"))
    )
    (net (code "27") (name "unconnected-(U$42-GND-Pad5)") (class "Default")
      (node (ref "U$42") (pin "5") (pinfunction "GND_5") (pintype "bidirectional"))
    )
    (net (code "28") (name "unconnected-(U$42-VCC-Pad8)") (class "Default")
      (node (ref "U$42") (pin "8") (pinfunction "VCC_8") (pintype "bidirectional"))
    )
    (net (code "29") (name "unconnected-(U$42-VIOUT-Pad7)") (class "Default")
      (node (ref "U$42") (pin "7") (pinfunction "VIOUT_7") (pintype "bidirectional"))
    )
  )
)
